# Sheet2.net
KiCad netlist of a schematic drawn in Altium Designer
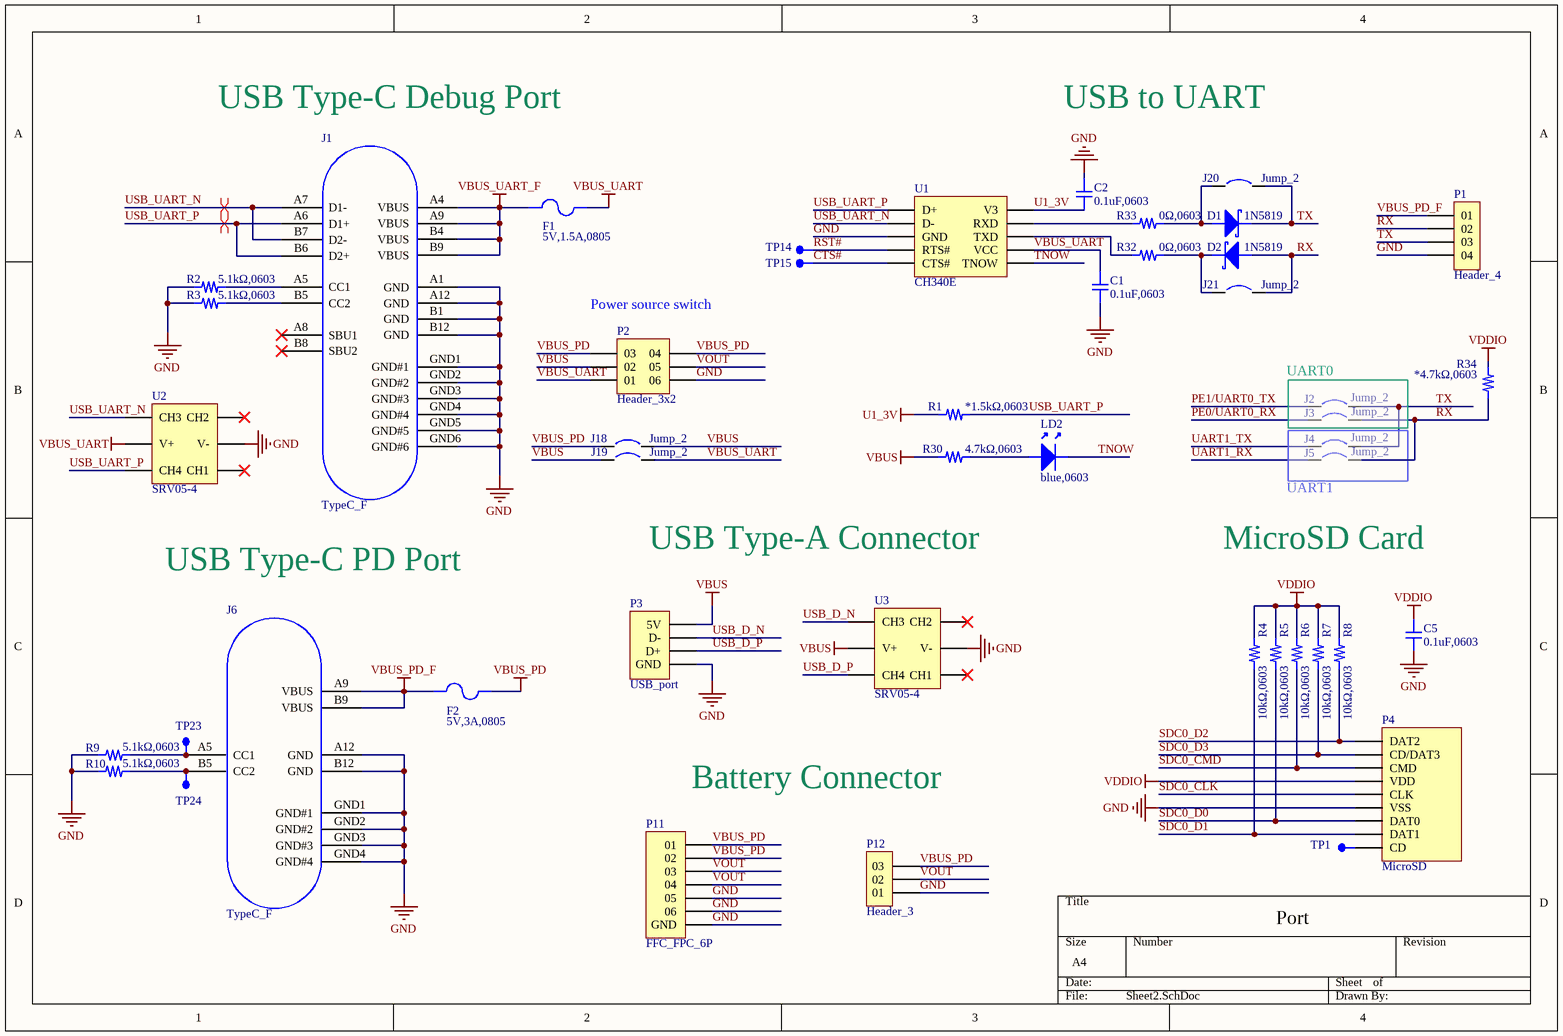
[diagram p0: Sheet2.SchDoc]

(export (version "E")
  (design (tool "Eeschema 10.0.6"))
  (components
    (comp (ref "C1") (value "0.1uF,0603") (footprint "C0603") (libsource (lib "myLib1") (part "Cap")))
    (comp (ref "C2") (value "0.1uF,0603") (footprint "C0603") (libsource (lib "myLib1") (part "Cap")))
    (comp (ref "C5") (value "0.1uF,0603") (footprint "C0603") (libsource (lib "myLib1") (part "Cap")))
    (comp (ref "D1")
      (value "1N5819")
      (footprint "SOD-323")
      (libsource (lib "myLib1") (part "Diode - Schottky"))
    )
    (comp (ref "D2")
      (value "1N5819")
      (footprint "SOD-323")
      (libsource (lib "myLib1") (part "Diode - Schottky"))
    )
    (comp (ref "F1") (value "5V,1.5A,0805") (footprint "F0805") (libsource (lib "myLib1") (part "Fuse")))
    (comp (ref "F2") (value "5V,3A,0805") (footprint "F0805") (libsource (lib "myLib1") (part "Fuse")))
    (comp (ref "J1")
      (value "TypeC_F")
      (footprint "Type-C_16P_F_0.5_BOTH")
      (description "Female SMD Connector")
      (libsource (lib "myLib1") (part "Type-C_16P_F_0.5"))
    )
    (comp (ref "J2") (value "Jump_2") (footprint "Jp_small") (libsource (lib "myLib1") (part "Jump_2")))
    (comp (ref "J3") (value "Jump_2") (footprint "Jp_small") (libsource (lib "myLib1") (part "Jump_2")))
    (comp (ref "J4") (value "Jump_2") (footprint "Jp_small") (libsource (lib "myLib1") (part "Jump_2")))
    (comp (ref "J5") (value "Jump_2") (footprint "Jp_small") (libsource (lib "myLib1") (part "Jump_2")))
    (comp (ref "J6")
      (value "TypeC_F")
      (footprint "Type-C_6P_F_BOTH")
      (description "Female SMD Connector")
      (libsource (lib "myLib1") (part "Type-C_6P_F_0.5"))
    )
    (comp (ref "J18") (value "Jump_2") (footprint "Jp_small") (libsource (lib "myLib1") (part "Jump_2")))
    (comp (ref "J19") (value "Jump_2") (footprint "Jp_small") (libsource (lib "myLib1") (part "Jump_2")))
    (comp (ref "J20") (value "Jump_2") (footprint "Jp_small") (libsource (lib "myLib1") (part "Jump_2")))
    (comp (ref "J21") (value "Jump_2") (footprint "Jp_small") (libsource (lib "myLib1") (part "Jump_2")))
    (comp (ref "LD2")
      (value "blue,0603")
      (footprint "LED0603")
      (libsource (lib "myLib1") (part "Diode - LED"))
    )
    (comp (ref "P1") (value "Header_4") (footprint "Header_4") (libsource (lib "myLib1") (part "Header_4")))
    (comp (ref "P2")
      (value "Header_3x2")
      (footprint "HEADER_3x2")
      (libsource (lib "myLib1") (part "Header_3x2"))
    )
    (comp (ref "P3")
      (value "USB_port")
      (footprint "USB-A-female-90")
      (libsource (lib "myLib1") (part "USB_port"))
    )
    (comp (ref "P4") (value "MicroSD") (footprint "MicroSD") (libsource (lib "myLib1") (part "MicroSD")))
    (comp (ref "P11")
      (value "FFC_FPC_6P")
      (footprint "FPC_1MM_6P")
      (libsource (lib "myLib1") (part "FFC_FPC_6P"))
    )
    (comp (ref "P12")
      (value "Header_3")
      (footprint "HEADER_3_2MM_SMD")
      (libsource (lib "myLib1") (part "Header_3"))
    )
    (comp (ref "R1") (value "*1.5kΩ,0603") (footprint "R0603") (libsource (lib "myLib1") (part "Res")))
    (comp (ref "R2") (value "5.1kΩ,0603") (footprint "R0603") (libsource (lib "myLib1") (part "Res")))
    (comp (ref "R3") (value "5.1kΩ,0603") (footprint "R0603") (libsource (lib "myLib1") (part "Res")))
    (comp (ref "R4") (value "10kΩ,0603") (footprint "R0603") (libsource (lib "myLib1") (part "Res")))
    (comp (ref "R5") (value "10kΩ,0603") (footprint "R0603") (libsource (lib "myLib1") (part "Res")))
    (comp (ref "R6") (value "10kΩ,0603") (footprint "R0603") (libsource (lib "myLib1") (part "Res")))
    (comp (ref "R7") (value "10kΩ,0603") (footprint "R0603") (libsource (lib "myLib1") (part "Res")))
    (comp (ref "R8") (value "10kΩ,0603") (footprint "R0603") (libsource (lib "myLib1") (part "Res")))
    (comp (ref "R9") (value "5.1kΩ,0603") (footprint "R0603") (libsource (lib "myLib1") (part "Res")))
    (comp (ref "R10") (value "5.1kΩ,0603") (footprint "R0603") (libsource (lib "myLib1") (part "Res")))
    (comp (ref "R30") (value "4.7kΩ,0603") (footprint "R0603") (libsource (lib "myLib1") (part "Res")))
    (comp (ref "R32") (value "0Ω,0603") (footprint "R0603") (libsource (lib "myLib1") (part "Res")))
    (comp (ref "R33") (value "0Ω,0603") (footprint "R0603") (libsource (lib "myLib1") (part "Res")))
    (comp (ref "R34") (value "*4.7kΩ,0603") (footprint "R0603") (libsource (lib "myLib1") (part "Res")))
    (comp (ref "TP1") (value "TP") (footprint "TP") (libsource (lib "myLib1") (part "TP")))
    (comp (ref "TP14") (value "TP") (footprint "TP") (libsource (lib "myLib1") (part "TP")))
    (comp (ref "TP15") (value "TP") (footprint "TP") (libsource (lib "myLib1") (part "TP")))
    (comp (ref "TP23") (value "TP") (footprint "TP") (libsource (lib "myLib1") (part "TP")))
    (comp (ref "TP24") (value "TP") (footprint "TP") (libsource (lib "myLib1") (part "TP")))
    (comp (ref "U1") (value "CH340E") (footprint "MSOP-10") (libsource (lib "myLib1") (part "CH340E")))
    (comp (ref "U2") (value "SRV05-4") (footprint "SOT23-6") (libsource (lib "myLib1") (part "SRV05-4")))
    (comp (ref "U3") (value "SRV05-4") (footprint "SOT23-6") (libsource (lib "myLib1") (part "SRV05-4")))
  )
  (nets
    (net (code "1") (name "/CTS#") (class "Default")
      (node (ref "TP15") (pin "01") (pintype "passive"))
      (node (ref "U1") (pin "05") (pinfunction "CTS#_05") (pintype "passive"))
    )
    (net (code "2") (name "/PE0{slash}UART0_RX") (class "Default")
      (node (ref "J3") (pin "01") (pinfunction "1_01") (pintype "passive"))
    )
    (net (code "3") (name "/PE1{slash}UART0_TX") (class "Default")
      (node (ref "J2") (pin "01") (pinfunction "1_01") (pintype "passive"))
    )
    (net (code "4") (name "/RST#") (class "Default")
      (node (ref "TP14") (pin "01") (pintype "passive"))
      (node (ref "U1") (pin "04") (pinfunction "RTS#_04") (pintype "passive"))
    )
    (net (code "5") (name "/RX") (class "Default")
      (node (ref "D2") (pin "01") (pintype "passive"))
      (node (ref "J21") (pin "02") (pinfunction "2_02") (pintype "passive"))
      (node (ref "J3") (pin "02") (pinfunction "2_02") (pintype "passive"))
      (node (ref "J5") (pin "02") (pinfunction "2_02") (pintype "passive"))
      (node (ref "P1") (pin "02") (pinfunction "02_02") (pintype "passive"))
      (node (ref "R34") (pin "01") (pintype "passive"))
    )
    (net (code "6") (name "/SDC0_CLK") (class "Default")
      (node (ref "P4") (pin "05") (pinfunction "CLK_05") (pintype "passive"))
    )
    (net (code "7") (name "/SDC0_CMD") (class "Default")
      (node (ref "P4") (pin "03") (pinfunction "CMD_03") (pintype "passive"))
      (node (ref "R6") (pin "02") (pintype "passive"))
    )
    (net (code "8") (name "/SDC0_D0") (class "Default")
      (node (ref "P4") (pin "07") (pinfunction "DAT0_07") (pintype "passive"))
      (node (ref "R5") (pin "02") (pintype "passive"))
    )
    (net (code "9") (name "/SDC0_D1") (class "Default")
      (node (ref "P4") (pin "08") (pinfunction "DAT1_08") (pintype "passive"))
      (node (ref "R4") (pin "02") (pintype "passive"))
    )
    (net (code "10") (name "/SDC0_D2") (class "Default")
      (node (ref "P4") (pin "01") (pinfunction "DAT2_01") (pintype "passive"))
      (node (ref "R8") (pin "02") (pintype "passive"))
    )
    (net (code "11") (name "/SDC0_D3") (class "Default")
      (node (ref "P4") (pin "02") (pinfunction "CD/DAT3_02") (pintype "passive"))
      (node (ref "R7") (pin "02") (pintype "passive"))
    )
    (net (code "12") (name "/TNOW") (class "Default")
      (node (ref "LD2") (pin "02") (pintype "passive"))
      (node (ref "U1") (pin "06") (pinfunction "TNOW_06") (pintype "passive"))
    )
    (net (code "13") (name "/TX") (class "Default")
      (node (ref "D1") (pin "02") (pintype "passive"))
      (node (ref "J2") (pin "02") (pinfunction "2_02") (pintype "passive"))
      (node (ref "J20") (pin "02") (pinfunction "2_02") (pintype "passive"))
      (node (ref "J4") (pin "02") (pinfunction "2_02") (pintype "passive"))
      (node (ref "P1") (pin "03") (pinfunction "03_03") (pintype "passive"))
    )
    (net (code "14") (name "/UART1_RX") (class "Default")
      (node (ref "J5") (pin "01") (pinfunction "1_01") (pintype "passive"))
    )
    (net (code "15") (name "/UART1_TX") (class "Default")
      (node (ref "J4") (pin "01") (pinfunction "1_01") (pintype "passive"))
    )
    (net (code "16") (name "/USB_D_N") (class "Default")
      (node (ref "P3") (pin "03") (pinfunction "D-_03") (pintype "passive"))
      (node (ref "U3") (pin "04") (pinfunction "CH3_04") (pintype "passive"))
    )
    (net (code "17") (name "/USB_D_P") (class "Default")
      (node (ref "P3") (pin "02") (pinfunction "D+_02") (pintype "passive"))
      (node (ref "U3") (pin "06") (pinfunction "CH4_06") (pintype "passive"))
    )
    (net (code "18") (name "/USB_UART_N") (class "Default")
      (node (ref "J1") (pin "A7") (pinfunction "D1-_A7") (pintype "passive"))
      (node (ref "J1") (pin "B7") (pinfunction "D2-_B7") (pintype "passive"))
      (node (ref "U1") (pin "02") (pinfunction "D-_02") (pintype "passive"))
      (node (ref "U2") (pin "04") (pinfunction "CH3_04") (pintype "passive"))
    )
    (net (code "19") (name "/USB_UART_P") (class "Default")
      (node (ref "J1") (pin "A6") (pinfunction "D1+_A6") (pintype "passive"))
      (node (ref "J1") (pin "B6") (pinfunction "D2+_B6") (pintype "passive"))
      (node (ref "R1") (pin "01") (pintype "passive"))
      (node (ref "U1") (pin "01") (pinfunction "D+_01") (pintype "passive"))
      (node (ref "U2") (pin "06") (pinfunction "CH4_06") (pintype "passive"))
    )
    (net (code "20") (name "/VOUT") (class "Default")
      (node (ref "P11") (pin "03") (pinfunction "03_03") (pintype "passive"))
      (node (ref "P11") (pin "04") (pinfunction "04_04") (pintype "passive"))
      (node (ref "P12") (pin "02") (pinfunction "02_02") (pintype "passive"))
      (node (ref "P2") (pin "05") (pinfunction "05_05") (pintype "passive"))
    )
    (net (code "21") (name "GND") (class "Default")
      (node (ref "C1") (pin "02") (pintype "passive"))
      (node (ref "C2") (pin "01") (pintype "passive"))
      (node (ref "C5") (pin "01") (pintype "passive"))
      (node (ref "J1") (pin "A1") (pinfunction "GND_A1") (pintype "power_in"))
      (node (ref "J1") (pin "A12") (pinfunction "GND_A12") (pintype "power_in"))
      (node (ref "J1") (pin "B1") (pinfunction "GND_B1") (pintype "power_in"))
      (node (ref "J1") (pin "B12") (pinfunction "GND_B12") (pintype "power_in"))
      (node (ref "J1") (pin "GND1") (pinfunction "GND#1_GND1") (pintype "passive"))
      (node (ref "J1") (pin "GND2") (pinfunction "GND#2_GND2") (pintype "passive"))
      (node (ref "J1") (pin "GND3") (pinfunction "GND#3_GND3") (pintype "passive"))
      (node (ref "J1") (pin "GND4") (pinfunction "GND#4_GND4") (pintype "passive"))
      (node (ref "J1") (pin "GND5") (pinfunction "GND#5_GND5") (pintype "passive"))
      (node (ref "J1") (pin "GND6") (pinfunction "GND#6_GND6") (pintype "passive"))
      (node (ref "J6") (pin "A12") (pinfunction "GND_A12") (pintype "power_in"))
      (node (ref "J6") (pin "B12") (pinfunction "GND_B12") (pintype "power_in"))
      (node (ref "J6") (pin "GND1") (pinfunction "GND#1_GND1") (pintype "passive"))
      (node (ref "J6") (pin "GND2") (pinfunction "GND#2_GND2") (pintype "passive"))
      (node (ref "J6") (pin "GND3") (pinfunction "GND#3_GND3") (pintype "passive"))
      (node (ref "J6") (pin "GND4") (pinfunction "GND#4_GND4") (pintype "passive"))
      (node (ref "P1") (pin "04") (pinfunction "04_04") (pintype "passive"))
      (node (ref "P11") (pin "0") (pinfunction "GND_0") (pintype "passive"))
      (node (ref "P11") (pin "05") (pinfunction "05_05") (pintype "passive"))
      (node (ref "P11") (pin "06") (pinfunction "06_06") (pintype "passive"))
      (node (ref "P12") (pin "01") (pinfunction "01_01") (pintype "passive"))
      (node (ref "P2") (pin "06") (pinfunction "06_06") (pintype "passive"))
      (node (ref "P3") (pin "01") (pinfunction "GND_01") (pintype "passive"))
      (node (ref "P4") (pin "06") (pinfunction "VSS_06") (pintype "passive"))
      (node (ref "R10") (pin "01") (pintype "passive"))
      (node (ref "R2") (pin "01") (pintype "passive"))
      (node (ref "R3") (pin "01") (pintype "passive"))
      (node (ref "R9") (pin "01") (pintype "passive"))
      (node (ref "U1") (pin "03") (pinfunction "GND_03") (pintype "passive"))
      (node (ref "U2") (pin "02") (pinfunction "V-_02") (pintype "passive"))
      (node (ref "U3") (pin "02") (pinfunction "V-_02") (pintype "passive"))
    )
    (net (code "22") (name "Net-(J1-CC1)") (class "Default")
      (node (ref "J1") (pin "A5") (pinfunction "CC1_A5") (pintype "passive"))
      (node (ref "R2") (pin "02") (pintype "passive"))
    )
    (net (code "23") (name "Net-(J1-CC2)") (class "Default")
      (node (ref "J1") (pin "B5") (pinfunction "CC2_B5") (pintype "passive"))
      (node (ref "R3") (pin "02") (pintype "passive"))
    )
    (net (code "24") (name "Net-(J6-CC1)") (class "Default")
      (node (ref "J6") (pin "A5") (pinfunction "CC1_A5") (pintype "passive"))
      (node (ref "R9") (pin "02") (pintype "passive"))
      (node (ref "TP23") (pin "01") (pintype "passive"))
    )
    (net (code "25") (name "Net-(J6-CC2)") (class "Default")
      (node (ref "J6") (pin "B5") (pinfunction "CC2_B5") (pintype "passive"))
      (node (ref "R10") (pin "02") (pintype "passive"))
      (node (ref "TP24") (pin "01") (pintype "passive"))
    )
    (net (code "26") (name "Net-(J20-1)") (class "Default")
      (node (ref "D1") (pin "01") (pintype "passive"))
      (node (ref "J20") (pin "01") (pinfunction "1_01") (pintype "passive"))
      (node (ref "R33") (pin "02") (pintype "passive"))
    )
    (net (code "27") (name "Net-(J21-1)") (class "Default")
      (node (ref "D2") (pin "02") (pintype "passive"))
      (node (ref "J21") (pin "01") (pinfunction "1_01") (pintype "passive"))
      (node (ref "R32") (pin "02") (pintype "passive"))
    )
    (net (code "28") (name "Net-(LD2-Pad01)") (class "Default")
      (node (ref "LD2") (pin "01") (pintype "passive"))
      (node (ref "R30") (pin "02") (pintype "passive"))
    )
    (net (code "29") (name "Net-(P4-CD)") (class "Default")
      (node (ref "P4") (pin "09") (pinfunction "CD_09") (pintype "passive"))
      (node (ref "TP1") (pin "01") (pintype "passive"))
    )
    (net (code "30") (name "Net-(U1-RXD)") (class "Default")
      (node (ref "R33") (pin "01") (pintype "passive"))
      (node (ref "U1") (pin "09") (pinfunction "RXD_09") (pintype "passive"))
    )
    (net (code "31") (name "Net-(U1-TXD)") (class "Default")
      (node (ref "R32") (pin "01") (pintype "passive"))
      (node (ref "U1") (pin "08") (pinfunction "TXD_08") (pintype "passive"))
    )
    (net (code "32") (name "U1_3V") (class "Default")
      (node (ref "C2") (pin "02") (pintype "passive"))
      (node (ref "R1") (pin "02") (pintype "passive"))
      (node (ref "U1") (pin "10") (pinfunction "V3_10") (pintype "passive"))
    )
    (net (code "33") (name "VBUS") (class "Default")
      (node (ref "J18") (pin "02") (pinfunction "2_02") (pintype "passive"))
      (node (ref "J19") (pin "01") (pinfunction "1_01") (pintype "passive"))
      (node (ref "P2") (pin "02") (pinfunction "02_02") (pintype "passive"))
      (node (ref "P3") (pin "04") (pinfunction "5V_04") (pintype "passive"))
      (node (ref "R30") (pin "01") (pintype "passive"))
      (node (ref "U3") (pin "05") (pinfunction "V+_05") (pintype "passive"))
    )
    (net (code "34") (name "VBUS_PD") (class "Default")
      (node (ref "F2") (pin "02") (pintype "passive"))
      (node (ref "J18") (pin "01") (pinfunction "1_01") (pintype "passive"))
      (node (ref "P11") (pin "01") (pinfunction "01_01") (pintype "passive"))
      (node (ref "P11") (pin "02") (pinfunction "02_02") (pintype "passive"))
      (node (ref "P12") (pin "03") (pinfunction "03_03") (pintype "passive"))
      (node (ref "P2") (pin "03") (pinfunction "03_03") (pintype "passive"))
      (node (ref "P2") (pin "04") (pinfunction "04_04") (pintype "passive"))
    )
    (net (code "35") (name "VBUS_PD_F") (class "Default")
      (node (ref "F2") (pin "01") (pintype "passive"))
      (node (ref "J6") (pin "A9") (pinfunction "VBUS_A9") (pintype "power_in"))
      (node (ref "J6") (pin "B9") (pinfunction "VBUS_B9") (pintype "power_in"))
      (node (ref "P1") (pin "01") (pinfunction "01_01") (pintype "passive"))
    )
    (net (code "36") (name "VBUS_UART") (class "Default")
      (node (ref "C1") (pin "01") (pintype "passive"))
      (node (ref "F1") (pin "02") (pintype "passive"))
      (node (ref "J19") (pin "02") (pinfunction "2_02") (pintype "passive"))
      (node (ref "P2") (pin "01") (pinfunction "01_01") (pintype "passive"))
      (node (ref "U1") (pin "07") (pinfunction "VCC_07") (pintype "passive"))
      (node (ref "U2") (pin "05") (pinfunction "V+_05") (pintype "passive"))
    )
    (net (code "37") (name "VBUS_UART_F") (class "Default")
      (node (ref "F1") (pin "01") (pintype "passive"))
      (node (ref "J1") (pin "A4") (pinfunction "VBUS_A4") (pintype "power_in"))
      (node (ref "J1") (pin "A9") (pinfunction "VBUS_A9") (pintype "power_in"))
      (node (ref "J1") (pin "B4") (pinfunction "VBUS_B4") (pintype "power_in"))
      (node (ref "J1") (pin "B9") (pinfunction "VBUS_B9") (pintype "power_in"))
    )
    (net (code "38") (name "VDDIO") (class "Default")
      (node (ref "C5") (pin "02") (pintype "passive"))
      (node (ref "P4") (pin "04") (pinfunction "VDD_04") (pintype "passive"))
      (node (ref "R34") (pin "02") (pintype "passive"))
      (node (ref "R4") (pin "01") (pintype "passive"))
      (node (ref "R5") (pin "01") (pintype "passive"))
      (node (ref "R6") (pin "01") (pintype "passive"))
      (node (ref "R7") (pin "01") (pintype "passive"))
      (node (ref "R8") (pin "01") (pintype "passive"))
    )
    (net (code "39") (name "unconnected-(J1-SBU1-PadA8)") (class "Default")
      (node (ref "J1") (pin "A8") (pinfunction "SBU1_A8") (pintype "passive+no_connect"))
    )
    (net (code "40") (name "unconnected-(J1-SBU2-PadB8)") (class "Default")
      (node (ref "J1") (pin "B8") (pinfunction "SBU2_B8") (pintype "passive+no_connect"))
    )
    (net (code "41") (name "unconnected-(U2-CH1-Pad01)") (class "Default")
      (node (ref "U2") (pin "01") (pinfunction "CH1_01") (pintype "passive+no_connect"))
    )
    (net (code "42") (name "unconnected-(U2-CH2-Pad03)") (class "Default")
      (node (ref "U2") (pin "03") (pinfunction "CH2_03") (pintype "passive+no_connect"))
    )
    (net (code "43") (name "unconnected-(U3-CH1-Pad01)") (class "Default")
      (node (ref "U3") (pin "01") (pinfunction "CH1_01") (pintype "passive+no_connect"))
    )
    (net (code "44") (name "unconnected-(U3-CH2-Pad03)") (class "Default")
      (node (ref "U3") (pin "03") (pinfunction "CH2_03") (pintype "passive+no_connect"))
    )
  )
)
